# Macropad-Advanced.net
KiCad netlist of a schematic drawn in EasyEDA Pro
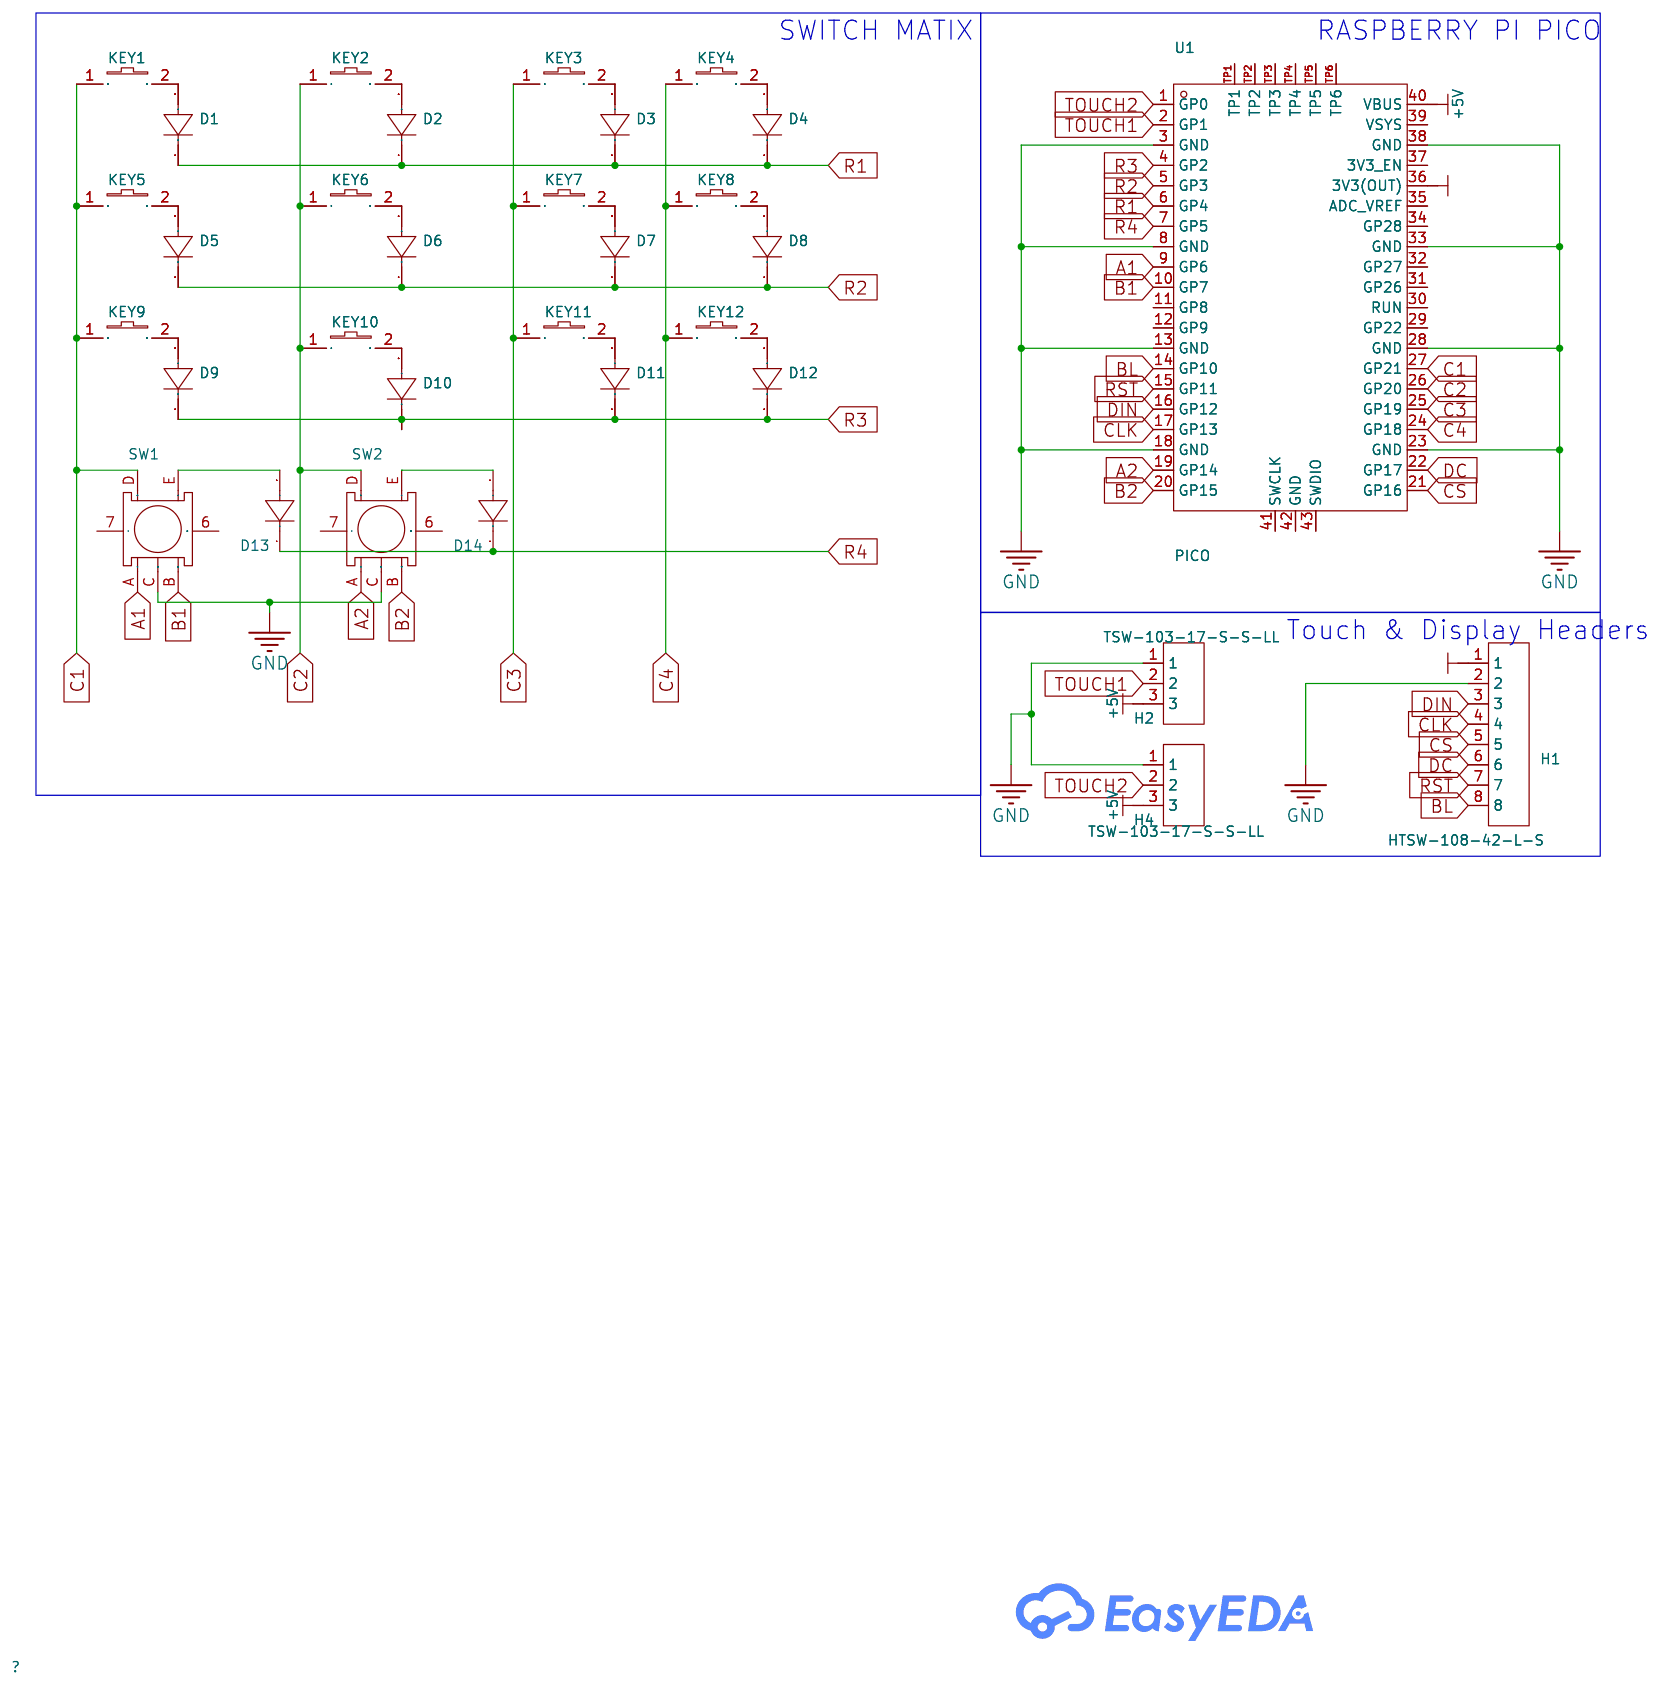
[diagram p0: schematic sheet]

(export (version "E")
  (design (tool "Eeschema 10.0.6"))
  (components
    (comp (ref "D1")
      (value "~")
      (footprint "easyedapro:DO-41_BD2.4-L4.7-P8.70-D0.9-RD")
      (fields (field (name "Manufacturer Part") "1N4148") (field (name "Manufacturer") "ST(先科)"))
      (libsource (lib "easyedapro") (part "D_1N4007"))
    )
    (comp (ref "D2")
      (value "~")
      (footprint "easyedapro:DO-41_BD2.4-L4.7-P8.70-D0.9-RD")
      (fields (field (name "Manufacturer Part") "1N4148") (field (name "Manufacturer") "ST(先科)"))
      (libsource (lib "easyedapro") (part "D_1N4007"))
    )
    (comp (ref "D3")
      (value "~")
      (footprint "easyedapro:DO-41_BD2.4-L4.7-P8.70-D0.9-RD")
      (fields (field (name "Manufacturer Part") "1N4148") (field (name "Manufacturer") "ST(先科)"))
      (libsource (lib "easyedapro") (part "D_1N4007"))
    )
    (comp (ref "D4")
      (value "~")
      (footprint "easyedapro:DO-41_BD2.4-L4.7-P8.70-D0.9-RD")
      (fields (field (name "Manufacturer Part") "1N4148") (field (name "Manufacturer") "ST(先科)"))
      (libsource (lib "easyedapro") (part "D_1N4007"))
    )
    (comp (ref "D5")
      (value "~")
      (footprint "easyedapro:DO-41_BD2.4-L4.7-P8.70-D0.9-RD")
      (fields (field (name "Manufacturer Part") "1N4148") (field (name "Manufacturer") "ST(先科)"))
      (libsource (lib "easyedapro") (part "D_1N4007"))
    )
    (comp (ref "D6")
      (value "~")
      (footprint "easyedapro:DO-41_BD2.4-L4.7-P8.70-D0.9-RD")
      (fields (field (name "Manufacturer Part") "1N4148") (field (name "Manufacturer") "ST(先科)"))
      (libsource (lib "easyedapro") (part "D_1N4007"))
    )
    (comp (ref "D7")
      (value "~")
      (footprint "easyedapro:DO-41_BD2.4-L4.7-P8.70-D0.9-RD")
      (fields (field (name "Manufacturer Part") "1N4148") (field (name "Manufacturer") "ST(先科)"))
      (libsource (lib "easyedapro") (part "D_1N4007"))
    )
    (comp (ref "D8")
      (value "~")
      (footprint "easyedapro:DO-41_BD2.4-L4.7-P8.70-D0.9-RD")
      (fields (field (name "Manufacturer Part") "1N4148") (field (name "Manufacturer") "ST(先科)"))
      (libsource (lib "easyedapro") (part "D_1N4007"))
    )
    (comp (ref "D9")
      (value "~")
      (footprint "easyedapro:DO-41_BD2.4-L4.7-P8.70-D0.9-RD")
      (fields (field (name "Manufacturer Part") "1N4148") (field (name "Manufacturer") "ST(先科)"))
      (libsource (lib "easyedapro") (part "D_1N4007"))
    )
    (comp (ref "D10")
      (value "~")
      (footprint "easyedapro:DO-41_BD2.4-L4.7-P8.70-D0.9-RD")
      (fields (field (name "Manufacturer Part") "1N4148") (field (name "Manufacturer") "ST(先科)"))
      (libsource (lib "easyedapro") (part "D_1N4007"))
    )
    (comp (ref "D11")
      (value "~")
      (footprint "easyedapro:DO-41_BD2.4-L4.7-P8.70-D0.9-RD")
      (fields (field (name "Manufacturer Part") "1N4148") (field (name "Manufacturer") "ST(先科)"))
      (libsource (lib "easyedapro") (part "D_1N4007"))
    )
    (comp (ref "D12")
      (value "~")
      (footprint "easyedapro:DO-41_BD2.4-L4.7-P8.70-D0.9-RD")
      (fields (field (name "Manufacturer Part") "1N4148") (field (name "Manufacturer") "ST(先科)"))
      (libsource (lib "easyedapro") (part "D_1N4007"))
    )
    (comp (ref "D13")
      (value "~")
      (footprint "easyedapro:DO-41_BD2.4-L4.7-P8.70-D0.9-RD")
      (fields (field (name "Manufacturer Part") "1N4148") (field (name "Manufacturer") "ST(先科)"))
      (libsource (lib "easyedapro") (part "D_1N4007"))
    )
    (comp (ref "D14")
      (value "~")
      (footprint "easyedapro:DO-41_BD2.4-L4.7-P8.70-D0.9-RD")
      (fields (field (name "Manufacturer Part") "1N4148") (field (name "Manufacturer") "ST(先科)"))
      (libsource (lib "easyedapro") (part "D_1N4007"))
    )
    (comp (ref "H1")
      (value "HTSW-108-42-L-S")
      (footprint "easyedapro:HDR-TH_8P-P2.54-V-M")
      (fields (field (name "Manufacturer") "SAMTEC"))
      (libsource (lib "easyedapro") (part "HTSW-108-42-L-S"))
    )
    (comp (ref "H2")
      (value "TSW-103-17-S-S-LL")
      (footprint "easyedapro:HDR-TH_3P-P2.54-V-M_HTSW-103-07-F-S")
      (fields (field (name "Manufacturer") "SAMTEC"))
      (libsource (lib "easyedapro") (part "TSW-103-17-S-S-LL"))
    )
    (comp (ref "H4")
      (value "TSW-103-17-S-S-LL")
      (footprint "easyedapro:HDR-TH_3P-P2.54-V-M_HTSW-103-07-F-S")
      (fields (field (name "Manufacturer") "SAMTEC"))
      (libsource (lib "easyedapro") (part "TSW-103-17-S-S-LL"))
    )
    (comp (ref "KEY1")
      (value "28115182DM")
      (footprint "easyedapro:KEY-TH_28115181DM")
      (fields (field (name "Manufacturer") "SAMZO(三佐)"))
      (libsource (lib "easyedapro") (part "28115182DM"))
    )
    (comp (ref "KEY2")
      (value "28115182DM")
      (footprint "easyedapro:KEY-TH_28115181DM")
      (fields (field (name "Manufacturer") "SAMZO(三佐)"))
      (libsource (lib "easyedapro") (part "28115182DM"))
    )
    (comp (ref "KEY3")
      (value "28115182DM")
      (footprint "easyedapro:KEY-TH_28115181DM")
      (fields (field (name "Manufacturer") "SAMZO(三佐)"))
      (libsource (lib "easyedapro") (part "28115182DM"))
    )
    (comp (ref "KEY4")
      (value "28115182DM")
      (footprint "easyedapro:KEY-TH_28115181DM")
      (fields (field (name "Manufacturer") "SAMZO(三佐)"))
      (libsource (lib "easyedapro") (part "28115182DM"))
    )
    (comp (ref "KEY5")
      (value "28115182DM")
      (footprint "easyedapro:KEY-TH_28115181DM")
      (fields (field (name "Manufacturer") "SAMZO(三佐)"))
      (libsource (lib "easyedapro") (part "28115182DM"))
    )
    (comp (ref "KEY6")
      (value "28115182DM")
      (footprint "easyedapro:KEY-TH_28115181DM")
      (fields (field (name "Manufacturer") "SAMZO(三佐)"))
      (libsource (lib "easyedapro") (part "28115182DM"))
    )
    (comp (ref "KEY7")
      (value "28115182DM")
      (footprint "easyedapro:KEY-TH_28115181DM")
      (fields (field (name "Manufacturer") "SAMZO(三佐)"))
      (libsource (lib "easyedapro") (part "28115182DM"))
    )
    (comp (ref "KEY8")
      (value "28115182DM")
      (footprint "easyedapro:KEY-TH_28115181DM")
      (fields (field (name "Manufacturer") "SAMZO(三佐)"))
      (libsource (lib "easyedapro") (part "28115182DM"))
    )
    (comp (ref "KEY9")
      (value "28115182DM")
      (footprint "easyedapro:KEY-TH_28115181DM")
      (fields (field (name "Manufacturer") "SAMZO(三佐)"))
      (libsource (lib "easyedapro") (part "28115182DM"))
    )
    (comp (ref "KEY10")
      (value "28115182DM")
      (footprint "easyedapro:KEY-TH_28115181DM")
      (fields (field (name "Manufacturer") "SAMZO(三佐)"))
      (libsource (lib "easyedapro") (part "28115182DM"))
    )
    (comp (ref "KEY11")
      (value "28115182DM")
      (footprint "easyedapro:KEY-TH_28115181DM")
      (fields (field (name "Manufacturer") "SAMZO(三佐)"))
      (libsource (lib "easyedapro") (part "28115182DM"))
    )
    (comp (ref "KEY12")
      (value "28115182DM")
      (footprint "easyedapro:KEY-TH_28115181DM")
      (fields (field (name "Manufacturer") "SAMZO(三佐)"))
      (libsource (lib "easyedapro") (part "28115182DM"))
    )
    (comp (ref "SW1")
      (value "EC11E09244BS")
      (footprint "easyedapro:SW-TH_EC11XXXXXXXX")
      (fields (field (name "Manufacturer") "ALPSALPINE(阿尔卑斯阿尔派)"))
      (libsource (lib "easyedapro") (part "EC11E09244BS"))
    )
    (comp (ref "SW2")
      (value "EC11E09244BS")
      (footprint "easyedapro:SW-TH_EC11XXXXXXXX")
      (fields (field (name "Manufacturer") "ALPSALPINE(阿尔卑斯阿尔派)"))
      (libsource (lib "easyedapro") (part "EC11E09244BS"))
    )
    (comp (ref "U1")
      (value "PICO")
      (footprint "easyedapro:COMM-SMD_L51.0-W21.0-P2.54_SC0916")
      (fields (field (name "Manufacturer") "Raspberry Pi(树莓派)"))
      (libsource (lib "easyedapro") (part "PICO"))
    )
  )
  (nets
    (net (code "1") (name "+5V") (class "Default")
      (node (ref "H2") (pin "3") (pinfunction "3_3") (pintype "unspecified"))
      (node (ref "H4") (pin "3") (pinfunction "3_3") (pintype "unspecified"))
      (node (ref "U1") (pin "40") (pinfunction "VBUS_40") (pintype "unspecified"))
    )
    (net (code "2") (name "3V3") (class "Default")
      (node (ref "H1") (pin "1") (pinfunction "1_1") (pintype "unspecified"))
      (node (ref "U1") (pin "36") (pinfunction "3V3(OUT)_36") (pintype "unspecified"))
    )
    (net (code "3") (name "A1") (class "Default")
      (node (ref "SW1") (pin "A") (pinfunction "A_A") (pintype "unspecified"))
      (node (ref "U1") (pin "9") (pinfunction "GP6_9") (pintype "unspecified"))
    )
    (net (code "4") (name "A2") (class "Default")
      (node (ref "SW2") (pin "A") (pinfunction "A_A") (pintype "unspecified"))
      (node (ref "U1") (pin "19") (pinfunction "GP14_19") (pintype "unspecified"))
    )
    (net (code "5") (name "B1") (class "Default")
      (node (ref "SW1") (pin "B") (pinfunction "B_B") (pintype "unspecified"))
      (node (ref "U1") (pin "10") (pinfunction "GP7_10") (pintype "unspecified"))
    )
    (net (code "6") (name "B2") (class "Default")
      (node (ref "SW2") (pin "B") (pinfunction "B_B") (pintype "unspecified"))
      (node (ref "U1") (pin "20") (pinfunction "GP15_20") (pintype "unspecified"))
    )
    (net (code "7") (name "BL") (class "Default")
      (node (ref "H1") (pin "8") (pinfunction "8_8") (pintype "unspecified"))
      (node (ref "U1") (pin "14") (pinfunction "GP10_14") (pintype "unspecified"))
    )
    (net (code "8") (name "C1") (class "Default")
      (node (ref "KEY1") (pin "1") (pinfunction "1_1") (pintype "unspecified"))
      (node (ref "KEY5") (pin "1") (pinfunction "1_1") (pintype "unspecified"))
      (node (ref "KEY9") (pin "1") (pinfunction "1_1") (pintype "unspecified"))
      (node (ref "SW1") (pin "D") (pinfunction "D_D") (pintype "unspecified"))
      (node (ref "U1") (pin "27") (pinfunction "GP21_27") (pintype "unspecified"))
    )
    (net (code "9") (name "C2") (class "Default")
      (node (ref "KEY10") (pin "1") (pinfunction "1_1") (pintype "unspecified"))
      (node (ref "KEY2") (pin "1") (pinfunction "1_1") (pintype "unspecified"))
      (node (ref "KEY6") (pin "1") (pinfunction "1_1") (pintype "unspecified"))
      (node (ref "SW2") (pin "D") (pinfunction "D_D") (pintype "unspecified"))
      (node (ref "U1") (pin "26") (pinfunction "GP20_26") (pintype "unspecified"))
    )
    (net (code "10") (name "C3") (class "Default")
      (node (ref "KEY11") (pin "1") (pinfunction "1_1") (pintype "unspecified"))
      (node (ref "KEY3") (pin "1") (pinfunction "1_1") (pintype "unspecified"))
      (node (ref "KEY7") (pin "1") (pinfunction "1_1") (pintype "unspecified"))
      (node (ref "U1") (pin "25") (pinfunction "GP19_25") (pintype "unspecified"))
    )
    (net (code "11") (name "C4") (class "Default")
      (node (ref "KEY12") (pin "1") (pinfunction "1_1") (pintype "unspecified"))
      (node (ref "KEY4") (pin "1") (pinfunction "1_1") (pintype "unspecified"))
      (node (ref "KEY8") (pin "1") (pinfunction "1_1") (pintype "unspecified"))
      (node (ref "U1") (pin "24") (pinfunction "GP18_24") (pintype "unspecified"))
    )
    (net (code "12") (name "CLK") (class "Default")
      (node (ref "H1") (pin "4") (pinfunction "4_4") (pintype "unspecified"))
      (node (ref "U1") (pin "17") (pinfunction "GP13_17") (pintype "unspecified"))
    )
    (net (code "13") (name "CS") (class "Default")
      (node (ref "H1") (pin "5") (pinfunction "5_5") (pintype "unspecified"))
      (node (ref "U1") (pin "21") (pinfunction "GP16_21") (pintype "unspecified"))
    )
    (net (code "14") (name "DC") (class "Default")
      (node (ref "H1") (pin "6") (pinfunction "6_6") (pintype "unspecified"))
      (node (ref "U1") (pin "22") (pinfunction "GP17_22") (pintype "unspecified"))
    )
    (net (code "15") (name "DIN") (class "Default")
      (node (ref "H1") (pin "3") (pinfunction "3_3") (pintype "unspecified"))
      (node (ref "U1") (pin "16") (pinfunction "GP12_16") (pintype "unspecified"))
    )
    (net (code "16") (name "GND") (class "Default")
      (node (ref "H1") (pin "2") (pinfunction "2_2") (pintype "unspecified"))
      (node (ref "H2") (pin "1") (pinfunction "1_1") (pintype "unspecified"))
      (node (ref "H4") (pin "1") (pinfunction "1_1") (pintype "unspecified"))
      (node (ref "SW1") (pin "C") (pinfunction "C_C") (pintype "unspecified"))
      (node (ref "SW2") (pin "C") (pinfunction "C_C") (pintype "unspecified"))
      (node (ref "U1") (pin "13") (pinfunction "GND_13") (pintype "unspecified"))
      (node (ref "U1") (pin "18") (pinfunction "GND_18") (pintype "unspecified"))
      (node (ref "U1") (pin "23") (pinfunction "GND_23") (pintype "unspecified"))
      (node (ref "U1") (pin "28") (pinfunction "GND_28") (pintype "unspecified"))
      (node (ref "U1") (pin "3") (pinfunction "GND_3") (pintype "unspecified"))
      (node (ref "U1") (pin "33") (pinfunction "GND_33") (pintype "unspecified"))
      (node (ref "U1") (pin "38") (pinfunction "GND_38") (pintype "unspecified"))
      (node (ref "U1") (pin "8") (pinfunction "GND_8") (pintype "unspecified"))
    )
    (net (code "17") (name "Net-(D1-A)") (class "Default")
      (node (ref "D1") (pin "2") (pinfunction "A_2") (pintype "input"))
      (node (ref "KEY1") (pin "2") (pinfunction "2_2") (pintype "unspecified"))
    )
    (net (code "18") (name "Net-(D2-A)") (class "Default")
      (node (ref "D2") (pin "2") (pinfunction "A_2") (pintype "input"))
      (node (ref "KEY2") (pin "2") (pinfunction "2_2") (pintype "unspecified"))
    )
    (net (code "19") (name "Net-(D3-A)") (class "Default")
      (node (ref "D3") (pin "2") (pinfunction "A_2") (pintype "input"))
      (node (ref "KEY3") (pin "2") (pinfunction "2_2") (pintype "unspecified"))
    )
    (net (code "20") (name "Net-(D4-A)") (class "Default")
      (node (ref "D4") (pin "2") (pinfunction "A_2") (pintype "input"))
      (node (ref "KEY4") (pin "2") (pinfunction "2_2") (pintype "unspecified"))
    )
    (net (code "21") (name "Net-(D5-A)") (class "Default")
      (node (ref "D5") (pin "2") (pinfunction "A_2") (pintype "input"))
      (node (ref "KEY5") (pin "2") (pinfunction "2_2") (pintype "unspecified"))
    )
    (net (code "22") (name "Net-(D6-A)") (class "Default")
      (node (ref "D6") (pin "2") (pinfunction "A_2") (pintype "input"))
      (node (ref "KEY6") (pin "2") (pinfunction "2_2") (pintype "unspecified"))
    )
    (net (code "23") (name "Net-(D7-A)") (class "Default")
      (node (ref "D7") (pin "2") (pinfunction "A_2") (pintype "input"))
      (node (ref "KEY7") (pin "2") (pinfunction "2_2") (pintype "unspecified"))
    )
    (net (code "24") (name "Net-(D8-A)") (class "Default")
      (node (ref "D8") (pin "2") (pinfunction "A_2") (pintype "input"))
      (node (ref "KEY8") (pin "2") (pinfunction "2_2") (pintype "unspecified"))
    )
    (net (code "25") (name "Net-(D9-A)") (class "Default")
      (node (ref "D9") (pin "2") (pinfunction "A_2") (pintype "input"))
      (node (ref "KEY9") (pin "2") (pinfunction "2_2") (pintype "unspecified"))
    )
    (net (code "26") (name "Net-(D10-A)") (class "Default")
      (node (ref "D10") (pin "2") (pinfunction "A_2") (pintype "input"))
      (node (ref "KEY10") (pin "2") (pinfunction "2_2") (pintype "unspecified"))
    )
    (net (code "27") (name "Net-(D11-A)") (class "Default")
      (node (ref "D11") (pin "2") (pinfunction "A_2") (pintype "input"))
      (node (ref "KEY11") (pin "2") (pinfunction "2_2") (pintype "unspecified"))
    )
    (net (code "28") (name "Net-(D12-A)") (class "Default")
      (node (ref "D12") (pin "2") (pinfunction "A_2") (pintype "input"))
      (node (ref "KEY12") (pin "2") (pinfunction "2_2") (pintype "unspecified"))
    )
    (net (code "29") (name "Net-(D13-A)") (class "Default")
      (node (ref "D13") (pin "2") (pinfunction "A_2") (pintype "input"))
      (node (ref "SW1") (pin "E") (pinfunction "E_E") (pintype "unspecified"))
    )
    (net (code "30") (name "Net-(D14-A)") (class "Default")
      (node (ref "D14") (pin "2") (pinfunction "A_2") (pintype "input"))
      (node (ref "SW2") (pin "E") (pinfunction "E_E") (pintype "unspecified"))
    )
    (net (code "31") (name "R1") (class "Default")
      (node (ref "D1") (pin "1") (pinfunction "K_1") (pintype "input"))
      (node (ref "D2") (pin "1") (pinfunction "K_1") (pintype "input"))
      (node (ref "D3") (pin "1") (pinfunction "K_1") (pintype "input"))
      (node (ref "D4") (pin "1") (pinfunction "K_1") (pintype "input"))
      (node (ref "U1") (pin "6") (pinfunction "GP4_6") (pintype "unspecified"))
    )
    (net (code "32") (name "R2") (class "Default")
      (node (ref "D5") (pin "1") (pinfunction "K_1") (pintype "input"))
      (node (ref "D6") (pin "1") (pinfunction "K_1") (pintype "input"))
      (node (ref "D7") (pin "1") (pinfunction "K_1") (pintype "input"))
      (node (ref "D8") (pin "1") (pinfunction "K_1") (pintype "input"))
      (node (ref "U1") (pin "5") (pinfunction "GP3_5") (pintype "unspecified"))
    )
    (net (code "33") (name "R3") (class "Default")
      (node (ref "D10") (pin "1") (pinfunction "K_1") (pintype "input"))
      (node (ref "D11") (pin "1") (pinfunction "K_1") (pintype "input"))
      (node (ref "D12") (pin "1") (pinfunction "K_1") (pintype "input"))
      (node (ref "D9") (pin "1") (pinfunction "K_1") (pintype "input"))
      (node (ref "U1") (pin "4") (pinfunction "GP2_4") (pintype "unspecified"))
    )
    (net (code "34") (name "R4") (class "Default")
      (node (ref "D13") (pin "1") (pinfunction "K_1") (pintype "input"))
      (node (ref "D14") (pin "1") (pinfunction "K_1") (pintype "input"))
      (node (ref "U1") (pin "7") (pinfunction "GP5_7") (pintype "unspecified"))
    )
    (net (code "35") (name "RST") (class "Default")
      (node (ref "H1") (pin "7") (pinfunction "7_7") (pintype "unspecified"))
      (node (ref "U1") (pin "15") (pinfunction "GP11_15") (pintype "unspecified"))
    )
    (net (code "36") (name "TOUCH1") (class "Default")
      (node (ref "H2") (pin "2") (pinfunction "2_2") (pintype "unspecified"))
      (node (ref "U1") (pin "2") (pinfunction "GP1_2") (pintype "unspecified"))
    )
    (net (code "37") (name "TOUCH2") (class "Default")
      (node (ref "H4") (pin "2") (pinfunction "2_2") (pintype "unspecified"))
      (node (ref "U1") (pin "1") (pinfunction "GP0_1") (pintype "unspecified"))
    )
    (net (code "38") (name "unconnected-(SW1-Pad6)") (class "Default")
      (node (ref "SW1") (pin "6") (pinfunction "6_6") (pintype "unspecified"))
    )
    (net (code "39") (name "unconnected-(SW1-Pad7)") (class "Default")
      (node (ref "SW1") (pin "7") (pinfunction "7_7") (pintype "unspecified"))
    )
    (net (code "40") (name "unconnected-(SW2-Pad6)") (class "Default")
      (node (ref "SW2") (pin "6") (pinfunction "6_6") (pintype "unspecified"))
    )
    (net (code "41") (name "unconnected-(SW2-Pad7)") (class "Default")
      (node (ref "SW2") (pin "7") (pinfunction "7_7") (pintype "unspecified"))
    )
    (net (code "42") (name "unconnected-(U1-3V3_EN-Pad37)") (class "Default")
      (node (ref "U1") (pin "37") (pinfunction "3V3_EN_37") (pintype "unspecified"))
    )
    (net (code "43") (name "unconnected-(U1-ADC_VREF-Pad35)") (class "Default")
      (node (ref "U1") (pin "35") (pinfunction "ADC_VREF_35") (pintype "unspecified"))
    )
    (net (code "44") (name "unconnected-(U1-GND-Pad42)") (class "Default")
      (node (ref "U1") (pin "42") (pinfunction "GND_42") (pintype "unspecified"))
    )
    (net (code "45") (name "unconnected-(U1-GP8-Pad11)") (class "Default")
      (node (ref "U1") (pin "11") (pinfunction "GP8_11") (pintype "unspecified"))
    )
    (net (code "46") (name "unconnected-(U1-GP9-Pad12)") (class "Default")
      (node (ref "U1") (pin "12") (pinfunction "GP9_12") (pintype "unspecified"))
    )
    (net (code "47") (name "unconnected-(U1-GP22-Pad29)") (class "Default")
      (node (ref "U1") (pin "29") (pinfunction "GP22_29") (pintype "unspecified"))
    )
    (net (code "48") (name "unconnected-(U1-GP26-Pad31)") (class "Default")
      (node (ref "U1") (pin "31") (pinfunction "GP26_31") (pintype "unspecified"))
    )
    (net (code "49") (name "unconnected-(U1-GP27-Pad32)") (class "Default")
      (node (ref "U1") (pin "32") (pinfunction "GP27_32") (pintype "unspecified"))
    )
    (net (code "50") (name "unconnected-(U1-GP28-Pad34)") (class "Default")
      (node (ref "U1") (pin "34") (pinfunction "GP28_34") (pintype "unspecified"))
    )
    (net (code "51") (name "unconnected-(U1-PadTP1)") (class "Default")
      (node (ref "U1") (pin "TP1") (pinfunction "TP1_TP1") (pintype "unspecified"))
    )
    (net (code "52") (name "unconnected-(U1-PadTP2)") (class "Default")
      (node (ref "U1") (pin "TP2") (pinfunction "TP2_TP2") (pintype "unspecified"))
    )
    (net (code "53") (name "unconnected-(U1-PadTP3)") (class "Default")
      (node (ref "U1") (pin "TP3") (pinfunction "TP3_TP3") (pintype "unspecified"))
    )
    (net (code "54") (name "unconnected-(U1-PadTP4)") (class "Default")
      (node (ref "U1") (pin "TP4") (pinfunction "TP4_TP4") (pintype "unspecified"))
    )
    (net (code "55") (name "unconnected-(U1-PadTP5)") (class "Default")
      (node (ref "U1") (pin "TP5") (pinfunction "TP5_TP5") (pintype "unspecified"))
    )
    (net (code "56") (name "unconnected-(U1-PadTP6)") (class "Default")
      (node (ref "U1") (pin "TP6") (pinfunction "TP6_TP6") (pintype "unspecified"))
    )
    (net (code "57") (name "unconnected-(U1-RUN-Pad30)") (class "Default")
      (node (ref "U1") (pin "30") (pinfunction "RUN_30") (pintype "unspecified"))
    )
    (net (code "58") (name "unconnected-(U1-SWCLK-Pad41)") (class "Default")
      (node (ref "U1") (pin "41") (pinfunction "SWCLK_41") (pintype "unspecified"))
    )
    (net (code "59") (name "unconnected-(U1-SWDIO-Pad43)") (class "Default")
      (node (ref "U1") (pin "43") (pinfunction "SWDIO_43") (pintype "unspecified"))
    )
    (net (code "60") (name "unconnected-(U1-VSYS-Pad39)") (class "Default")
      (node (ref "U1") (pin "39") (pinfunction "VSYS_39") (pintype "unspecified"))
    )
  )
)
